# Battery_Monitor_ESP.net
KiCad netlist of a schematic drawn in EAGLE
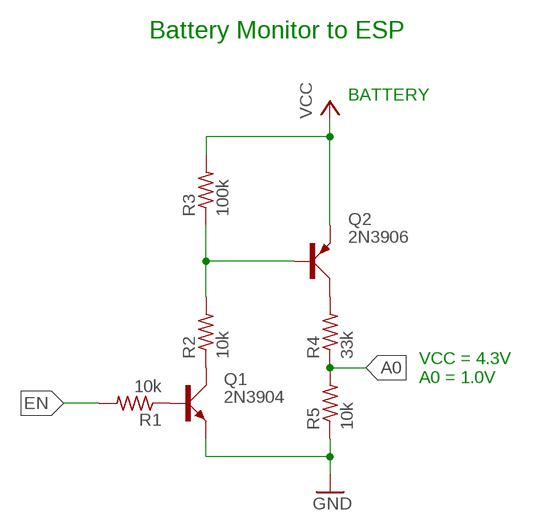
[diagram p0: schematic, sheet 1]

(export (version "E")
  (design (tool "Eeschema 10.0.6"))
  (components
    (comp (ref "Q1")
      (value "2N3904")
      (footprint "eagle-import:TO92D")
      (libsource (lib "eagle-import") (part "2N3904"))
    )
    (comp (ref "Q2")
      (value "2N3906")
      (footprint "eagle-import:TO92D")
      (libsource (lib "eagle-import") (part "2N3906"))
    )
    (comp (ref "R1")
      (value "10k")
      (footprint "eagle-import:0207_10")
      (libsource (lib "eagle-import") (part "R-US_0207/10"))
    )
    (comp (ref "R2")
      (value "10k")
      (footprint "eagle-import:0207_10")
      (libsource (lib "eagle-import") (part "R-US_0207/10"))
    )
    (comp (ref "R3")
      (value "100k")
      (footprint "eagle-import:0207_10")
      (libsource (lib "eagle-import") (part "R-US_0207/10"))
    )
    (comp (ref "R4")
      (value "33k")
      (footprint "eagle-import:0207_10")
      (libsource (lib "eagle-import") (part "R-US_0207/10"))
    )
    (comp (ref "R5")
      (value "10k")
      (footprint "eagle-import:0207_10")
      (libsource (lib "eagle-import") (part "R-US_0207/10"))
    )
  )
  (nets
    (net (code "1") (name "A0") (class "Default")
      (node (ref "R4") (pin "1") (pinfunction "1_1") (pintype "passive"))
      (node (ref "R5") (pin "2") (pinfunction "2_2") (pintype "passive"))
    )
    (net (code "2") (name "EN") (class "Default")
      (node (ref "R1") (pin "2") (pinfunction "2_2") (pintype "passive"))
    )
    (net (code "3") (name "GND") (class "Default")
      (node (ref "Q1") (pin "E") (pinfunction "E_E") (pintype "passive"))
      (node (ref "R5") (pin "1") (pinfunction "1_1") (pintype "passive"))
    )
    (net (code "4") (name "Net-(Q1-PadB)") (class "Default")
      (node (ref "Q1") (pin "B") (pinfunction "B_B") (pintype "passive"))
      (node (ref "R1") (pin "1") (pinfunction "1_1") (pintype "passive"))
    )
    (net (code "5") (name "Net-(Q1-PadC)") (class "Default")
      (node (ref "Q1") (pin "C") (pinfunction "C_C") (pintype "passive"))
      (node (ref "R2") (pin "1") (pinfunction "1_1") (pintype "passive"))
    )
    (net (code "6") (name "Net-(Q2-PadB)") (class "Default")
      (node (ref "Q2") (pin "B") (pinfunction "B_B") (pintype "passive"))
      (node (ref "R2") (pin "2") (pinfunction "2_2") (pintype "passive"))
      (node (ref "R3") (pin "1") (pinfunction "1_1") (pintype "passive"))
    )
    (net (code "7") (name "Net-(Q2-PadC)") (class "Default")
      (node (ref "Q2") (pin "C") (pinfunction "C_C") (pintype "passive"))
      (node (ref "R4") (pin "2") (pinfunction "2_2") (pintype "passive"))
    )
    (net (code "8") (name "VCC") (class "Default")
      (node (ref "Q2") (pin "E") (pinfunction "E_E") (pintype "passive"))
      (node (ref "R3") (pin "2") (pinfunction "2_2") (pintype "passive"))
    )
  )
)
